# adapters.net
KiCad netlist of a schematic drawn in EAGLE
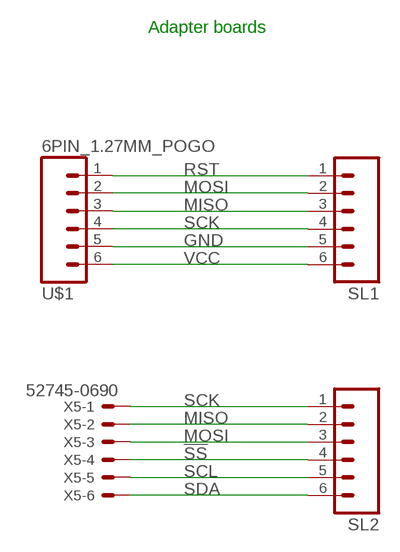
[diagram p0: schematic, sheet 1]

(export (version "E")
  (design (tool "Eeschema 10.0.6"))
  (components
    (comp (ref "SL1")
      (value "M06")
      (footprint "eagle-import:06P")
      (libsource (lib "eagle-import") (part "M06"))
    )
    (comp (ref "SL2")
      (value "M06")
      (footprint "eagle-import:06P")
      (libsource (lib "eagle-import") (part "M06"))
    )
    (comp (ref "U$1")
      (value "6PIN_1.27MM_POGO")
      (footprint "eagle-import:1X06-1.27MM_POGO")
      (libsource (lib "eagle-import") (part "6PIN_1.27MM_POGO"))
    )
    (comp (ref "X5")
      (value "52745-0690")
      (footprint "eagle-import:52745-0690")
      (fields (field (name "MF") "MOLEX"))
      (libsource (lib "eagle-import") (part "52745-0690"))
    )
  )
  (nets
    (net (code "1") (name "/GND") (class "Default")
      (node (ref "SL1") (pin "5") (pinfunction "5_5") (pintype "passive"))
      (node (ref "U$1") (pin "5") (pinfunction "5_5") (pintype "passive"))
    )
    (net (code "2") (name "/MISO") (class "Default")
      (node (ref "SL1") (pin "3") (pinfunction "3_3") (pintype "passive"))
      (node (ref "SL2") (pin "2") (pinfunction "2_2") (pintype "passive"))
      (node (ref "U$1") (pin "3") (pinfunction "3_3") (pintype "passive"))
      (node (ref "X5") (pin "2") (pinfunction "S_2") (pintype "passive"))
    )
    (net (code "3") (name "/MOSI") (class "Default")
      (node (ref "SL1") (pin "2") (pinfunction "2_2") (pintype "passive"))
      (node (ref "SL2") (pin "3") (pinfunction "3_3") (pintype "passive"))
      (node (ref "U$1") (pin "2") (pinfunction "2_2") (pintype "passive"))
      (node (ref "X5") (pin "3") (pinfunction "S_3") (pintype "passive"))
    )
    (net (code "4") (name "/RST") (class "Default")
      (node (ref "SL1") (pin "1") (pinfunction "1_1") (pintype "passive"))
      (node (ref "U$1") (pin "1") (pinfunction "1_1") (pintype "passive"))
    )
    (net (code "5") (name "/SCK") (class "Default")
      (node (ref "SL1") (pin "4") (pinfunction "4_4") (pintype "passive"))
      (node (ref "SL2") (pin "1") (pinfunction "1_1") (pintype "passive"))
      (node (ref "U$1") (pin "4") (pinfunction "4_4") (pintype "passive"))
      (node (ref "X5") (pin "1") (pinfunction "S_1") (pintype "passive"))
    )
    (net (code "6") (name "/SCL") (class "Default")
      (node (ref "SL2") (pin "5") (pinfunction "5_5") (pintype "passive"))
      (node (ref "X5") (pin "5") (pinfunction "S_5") (pintype "passive"))
    )
    (net (code "7") (name "/SDA") (class "Default")
      (node (ref "SL2") (pin "6") (pinfunction "6_6") (pintype "passive"))
      (node (ref "X5") (pin "6") (pinfunction "S_6") (pintype "passive"))
    )
    (net (code "8") (name "/VCC") (class "Default")
      (node (ref "SL1") (pin "6") (pinfunction "6_6") (pintype "passive"))
      (node (ref "U$1") (pin "6") (pinfunction "6_6") (pintype "passive"))
    )
    (net (code "9") (name "/~{SS}") (class "Default")
      (node (ref "SL2") (pin "4") (pinfunction "4_4") (pintype "passive"))
      (node (ref "X5") (pin "4") (pinfunction "S_4") (pintype "passive"))
    )
  )
)
